# LDR_Schematic.net
KiCad netlist of a schematic drawn in EAGLE
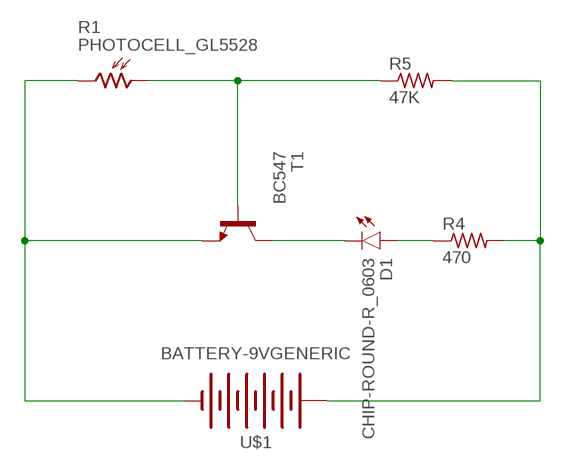
[diagram p0: schematic, sheet 1]

(export (version "E")
  (design (tool "Eeschema 10.0.6"))
  (components
    (comp (ref "D1")
      (value "CHIP-ROUND-R_0603")
      (footprint "eagle-import:LEDC1608X65N_RND-R")
      (libsource (lib "eagle-import") (part "CHIP-ROUND-R_0603"))
    )
    (comp (ref "R1")
      (value "PHOTOCELL_GL5528")
      (footprint "eagle-import:GL5528")
      (libsource (lib "eagle-import") (part "PHOTOCELL_GL5528"))
    )
    (comp (ref "R4")
      (value "470")
      (footprint "eagle-import:R0402")
      (libsource (lib "eagle-import") (part "R-US_R0402"))
    )
    (comp (ref "R5")
      (value "47K")
      (footprint "eagle-import:R0402")
      (libsource (lib "eagle-import") (part "R-US_R0402"))
    )
    (comp (ref "T1")
      (value "BC547")
      (footprint "eagle-import:TO92")
      (libsource (lib "eagle-import") (part "BC547"))
    )
    (comp (ref "U$1")
      (value "BATTERY-9VGENERIC")
      (footprint "eagle-import:BATTERY-GENERIC")
      (libsource (lib "eagle-import") (part "BATTERY-9VGENERIC"))
    )
  )
  (nets
    (net (code "1") (name "Net-(D1-PadA)") (class "Default")
      (node (ref "D1") (pin "A") (pinfunction "A_A") (pintype "passive"))
      (node (ref "R4") (pin "1") (pinfunction "1_1") (pintype "passive"))
    )
    (net (code "2") (name "Net-(R4-Pad2)") (class "Default")
      (node (ref "R4") (pin "2") (pinfunction "2_2") (pintype "passive"))
      (node (ref "R5") (pin "2") (pinfunction "2_2") (pintype "passive"))
      (node (ref "U$1") (pin "+") (pinfunction "+_+") (pintype "passive"))
    )
    (net (code "3") (name "Net-(T1-B)") (class "Default")
      (node (ref "R1") (pin "1") (pinfunction "1_1") (pintype "passive"))
      (node (ref "R5") (pin "1") (pinfunction "1_1") (pintype "passive"))
      (node (ref "T1") (pin "2") (pinfunction "B_2") (pintype "passive"))
    )
    (net (code "4") (name "Net-(T1-C)") (class "Default")
      (node (ref "D1") (pin "C") (pinfunction "C_C") (pintype "passive"))
      (node (ref "T1") (pin "3") (pinfunction "C_3") (pintype "passive"))
    )
    (net (code "5") (name "Net-(T1-E)") (class "Default")
      (node (ref "R1") (pin "2") (pinfunction "2_2") (pintype "passive"))
      (node (ref "T1") (pin "1") (pinfunction "E_1") (pintype "passive"))
      (node (ref "U$1") (pin "-") (pinfunction "-_-") (pintype "passive"))
    )
  )
)
